# PCB.net
KiCad netlist of a schematic drawn in EAGLE
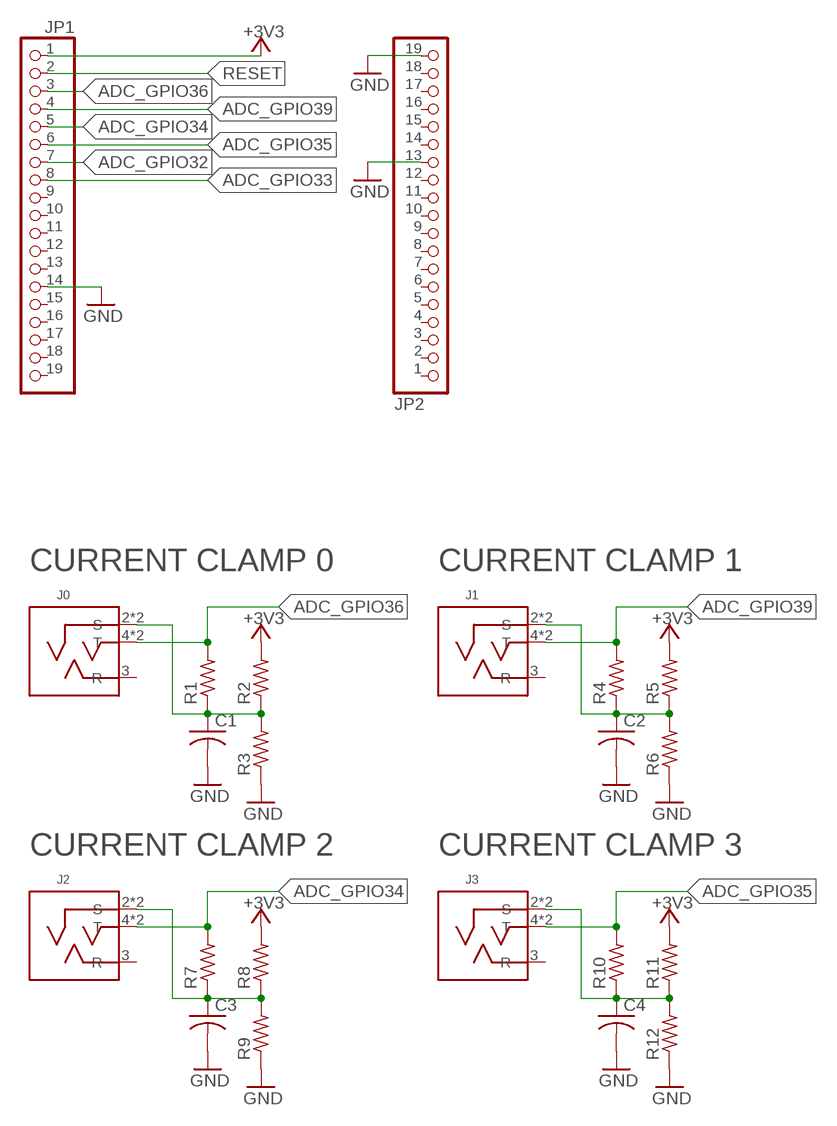
[diagram p0: schematic, sheet 1]

(export (version "E")
  (design (tool "Eeschema 10.0.6"))
  (components
    (comp (ref "C1")
      (value "C-USC1206")
      (footprint "eagle-import:C1206")
      (libsource (lib "eagle-import") (part "C-USC1206"))
    )
    (comp (ref "C2")
      (value "C-USC1206")
      (footprint "eagle-import:C1206")
      (libsource (lib "eagle-import") (part "C-USC1206"))
    )
    (comp (ref "C3")
      (value "C-USC1206")
      (footprint "eagle-import:C1206")
      (libsource (lib "eagle-import") (part "C-USC1206"))
    )
    (comp (ref "C4")
      (value "C-USC1206")
      (footprint "eagle-import:C1206")
      (libsource (lib "eagle-import") (part "C-USC1206"))
    )
    (comp (ref "J0")
      (value "BOOMELE_C18167")
      (footprint "eagle-import:PJ-313")
      (libsource (lib "eagle-import") (part "BOOMELE_C18167"))
    )
    (comp (ref "J1")
      (value "BOOMELE_C18167")
      (footprint "eagle-import:PJ-313")
      (libsource (lib "eagle-import") (part "BOOMELE_C18167"))
    )
    (comp (ref "J2")
      (value "BOOMELE_C18167")
      (footprint "eagle-import:PJ-313")
      (libsource (lib "eagle-import") (part "BOOMELE_C18167"))
    )
    (comp (ref "J3")
      (value "BOOMELE_C18167")
      (footprint "eagle-import:PJ-313")
      (libsource (lib "eagle-import") (part "BOOMELE_C18167"))
    )
    (comp (ref "JP1")
      (value "PINHD-1X19")
      (footprint "eagle-import:1X19")
      (libsource (lib "eagle-import") (part "PINHD-1X19"))
    )
    (comp (ref "JP2")
      (value "PINHD-1X19")
      (footprint "eagle-import:1X19")
      (libsource (lib "eagle-import") (part "PINHD-1X19"))
    )
    (comp (ref "R1")
      (value "R-US_R1206")
      (footprint "eagle-import:R1206")
      (libsource (lib "eagle-import") (part "R-US_R1206"))
    )
    (comp (ref "R2")
      (value "R-US_R1206")
      (footprint "eagle-import:R1206")
      (libsource (lib "eagle-import") (part "R-US_R1206"))
    )
    (comp (ref "R3")
      (value "R-US_R1206")
      (footprint "eagle-import:R1206")
      (libsource (lib "eagle-import") (part "R-US_R1206"))
    )
    (comp (ref "R4")
      (value "R-US_R1206")
      (footprint "eagle-import:R1206")
      (libsource (lib "eagle-import") (part "R-US_R1206"))
    )
    (comp (ref "R5")
      (value "R-US_R1206")
      (footprint "eagle-import:R1206")
      (libsource (lib "eagle-import") (part "R-US_R1206"))
    )
    (comp (ref "R6")
      (value "R-US_R1206")
      (footprint "eagle-import:R1206")
      (libsource (lib "eagle-import") (part "R-US_R1206"))
    )
    (comp (ref "R7")
      (value "R-US_R1206")
      (footprint "eagle-import:R1206")
      (libsource (lib "eagle-import") (part "R-US_R1206"))
    )
    (comp (ref "R8")
      (value "R-US_R1206")
      (footprint "eagle-import:R1206")
      (libsource (lib "eagle-import") (part "R-US_R1206"))
    )
    (comp (ref "R9")
      (value "R-US_R1206")
      (footprint "eagle-import:R1206")
      (libsource (lib "eagle-import") (part "R-US_R1206"))
    )
    (comp (ref "R10")
      (value "R-US_R1206")
      (footprint "eagle-import:R1206")
      (libsource (lib "eagle-import") (part "R-US_R1206"))
    )
    (comp (ref "R11")
      (value "R-US_R1206")
      (footprint "eagle-import:R1206")
      (libsource (lib "eagle-import") (part "R-US_R1206"))
    )
    (comp (ref "R12")
      (value "R-US_R1206")
      (footprint "eagle-import:R1206")
      (libsource (lib "eagle-import") (part "R-US_R1206"))
    )
  )
  (nets
    (net (code "1") (name "+3V3") (class "Default")
      (node (ref "JP1") (pin "1") (pinfunction "1_1") (pintype "passive"))
      (node (ref "R11") (pin "2") (pinfunction "2_2") (pintype "passive"))
      (node (ref "R2") (pin "2") (pinfunction "2_2") (pintype "passive"))
      (node (ref "R5") (pin "2") (pinfunction "2_2") (pintype "passive"))
      (node (ref "R8") (pin "2") (pinfunction "2_2") (pintype "passive"))
    )
    (net (code "2") (name "ADC_GPIO32") (class "Default")
      (node (ref "JP1") (pin "7") (pinfunction "7_7") (pintype "passive"))
    )
    (net (code "3") (name "ADC_GPIO33") (class "Default")
      (node (ref "JP1") (pin "8") (pinfunction "8_8") (pintype "passive"))
    )
    (net (code "4") (name "ADC_GPIO34") (class "Default")
      (node (ref "J2") (pin "4") (pinfunction "T_4") (pintype "bidirectional"))
      (node (ref "J2") (pin "4.") (pinfunction "T_4.") (pintype "bidirectional"))
      (node (ref "JP1") (pin "5") (pinfunction "5_5") (pintype "passive"))
      (node (ref "R7") (pin "2") (pinfunction "2_2") (pintype "passive"))
    )
    (net (code "5") (name "ADC_GPIO35") (class "Default")
      (node (ref "J3") (pin "4") (pinfunction "T_4") (pintype "bidirectional"))
      (node (ref "J3") (pin "4.") (pinfunction "T_4.") (pintype "bidirectional"))
      (node (ref "JP1") (pin "6") (pinfunction "6_6") (pintype "passive"))
      (node (ref "R10") (pin "2") (pinfunction "2_2") (pintype "passive"))
    )
    (net (code "6") (name "ADC_GPIO36") (class "Default")
      (node (ref "J0") (pin "4") (pinfunction "T_4") (pintype "bidirectional"))
      (node (ref "J0") (pin "4.") (pinfunction "T_4.") (pintype "bidirectional"))
      (node (ref "JP1") (pin "3") (pinfunction "3_3") (pintype "passive"))
      (node (ref "R1") (pin "2") (pinfunction "2_2") (pintype "passive"))
    )
    (net (code "7") (name "ADC_GPIO39") (class "Default")
      (node (ref "J1") (pin "4") (pinfunction "T_4") (pintype "bidirectional"))
      (node (ref "J1") (pin "4.") (pinfunction "T_4.") (pintype "bidirectional"))
      (node (ref "JP1") (pin "4") (pinfunction "4_4") (pintype "passive"))
      (node (ref "R4") (pin "2") (pinfunction "2_2") (pintype "passive"))
    )
    (net (code "8") (name "GND") (class "Default")
      (node (ref "C1") (pin "2") (pinfunction "2_2") (pintype "passive"))
      (node (ref "C2") (pin "2") (pinfunction "2_2") (pintype "passive"))
      (node (ref "C3") (pin "2") (pinfunction "2_2") (pintype "passive"))
      (node (ref "C4") (pin "2") (pinfunction "2_2") (pintype "passive"))
      (node (ref "JP1") (pin "14") (pinfunction "14_14") (pintype "passive"))
      (node (ref "JP2") (pin "13") (pinfunction "13_13") (pintype "passive"))
      (node (ref "JP2") (pin "19") (pinfunction "19_19") (pintype "passive"))
      (node (ref "R12") (pin "1") (pinfunction "1_1") (pintype "passive"))
      (node (ref "R3") (pin "1") (pinfunction "1_1") (pintype "passive"))
      (node (ref "R6") (pin "1") (pinfunction "1_1") (pintype "passive"))
      (node (ref "R9") (pin "1") (pinfunction "1_1") (pintype "passive"))
    )
    (net (code "9") (name "Net-(C1-Pad1)") (class "Default")
      (node (ref "C1") (pin "1") (pinfunction "1_1") (pintype "passive"))
      (node (ref "J0") (pin "2") (pinfunction "S_2") (pintype "bidirectional"))
      (node (ref "J0") (pin "2.") (pinfunction "S_2.") (pintype "bidirectional"))
      (node (ref "R1") (pin "1") (pinfunction "1_1") (pintype "passive"))
      (node (ref "R2") (pin "1") (pinfunction "1_1") (pintype "passive"))
      (node (ref "R3") (pin "2") (pinfunction "2_2") (pintype "passive"))
    )
    (net (code "10") (name "Net-(C2-Pad1)") (class "Default")
      (node (ref "C2") (pin "1") (pinfunction "1_1") (pintype "passive"))
      (node (ref "J1") (pin "2") (pinfunction "S_2") (pintype "bidirectional"))
      (node (ref "J1") (pin "2.") (pinfunction "S_2.") (pintype "bidirectional"))
      (node (ref "R4") (pin "1") (pinfunction "1_1") (pintype "passive"))
      (node (ref "R5") (pin "1") (pinfunction "1_1") (pintype "passive"))
      (node (ref "R6") (pin "2") (pinfunction "2_2") (pintype "passive"))
    )
    (net (code "11") (name "Net-(C3-Pad1)") (class "Default")
      (node (ref "C3") (pin "1") (pinfunction "1_1") (pintype "passive"))
      (node (ref "J2") (pin "2") (pinfunction "S_2") (pintype "bidirectional"))
      (node (ref "J2") (pin "2.") (pinfunction "S_2.") (pintype "bidirectional"))
      (node (ref "R7") (pin "1") (pinfunction "1_1") (pintype "passive"))
      (node (ref "R8") (pin "1") (pinfunction "1_1") (pintype "passive"))
      (node (ref "R9") (pin "2") (pinfunction "2_2") (pintype "passive"))
    )
    (net (code "12") (name "Net-(C4-Pad1)") (class "Default")
      (node (ref "C4") (pin "1") (pinfunction "1_1") (pintype "passive"))
      (node (ref "J3") (pin "2") (pinfunction "S_2") (pintype "bidirectional"))
      (node (ref "J3") (pin "2.") (pinfunction "S_2.") (pintype "bidirectional"))
      (node (ref "R10") (pin "1") (pinfunction "1_1") (pintype "passive"))
      (node (ref "R11") (pin "1") (pinfunction "1_1") (pintype "passive"))
      (node (ref "R12") (pin "2") (pinfunction "2_2") (pintype "passive"))
    )
    (net (code "13") (name "RESET") (class "Default")
      (node (ref "JP1") (pin "2") (pinfunction "2_2") (pintype "passive"))
    )
    (net (code "14") (name "unconnected-(J0-R-Pad3)") (class "Default")
      (node (ref "J0") (pin "3") (pinfunction "R_3") (pintype "bidirectional"))
    )
    (net (code "15") (name "unconnected-(J1-R-Pad3)") (class "Default")
      (node (ref "J1") (pin "3") (pinfunction "R_3") (pintype "bidirectional"))
    )
    (net (code "16") (name "unconnected-(J2-R-Pad3)") (class "Default")
      (node (ref "J2") (pin "3") (pinfunction "R_3") (pintype "bidirectional"))
    )
    (net (code "17") (name "unconnected-(J3-R-Pad3)") (class "Default")
      (node (ref "J3") (pin "3") (pinfunction "R_3") (pintype "bidirectional"))
    )
    (net (code "18") (name "unconnected-(JP1-Pad9)") (class "Default")
      (node (ref "JP1") (pin "9") (pinfunction "9_9") (pintype "passive"))
    )
    (net (code "19") (name "unconnected-(JP1-Pad10)") (class "Default")
      (node (ref "JP1") (pin "10") (pinfunction "10_10") (pintype "passive"))
    )
    (net (code "20") (name "unconnected-(JP1-Pad11)") (class "Default")
      (node (ref "JP1") (pin "11") (pinfunction "11_11") (pintype "passive"))
    )
    (net (code "21") (name "unconnected-(JP1-Pad12)") (class "Default")
      (node (ref "JP1") (pin "12") (pinfunction "12_12") (pintype "passive"))
    )
    (net (code "22") (name "unconnected-(JP1-Pad13)") (class "Default")
      (node (ref "JP1") (pin "13") (pinfunction "13_13") (pintype "passive"))
    )
    (net (code "23") (name "unconnected-(JP1-Pad15)") (class "Default")
      (node (ref "JP1") (pin "15") (pinfunction "15_15") (pintype "passive"))
    )
    (net (code "24") (name "unconnected-(JP1-Pad16)") (class "Default")
      (node (ref "JP1") (pin "16") (pinfunction "16_16") (pintype "passive"))
    )
    (net (code "25") (name "unconnected-(JP1-Pad17)") (class "Default")
      (node (ref "JP1") (pin "17") (pinfunction "17_17") (pintype "passive"))
    )
    (net (code "26") (name "unconnected-(JP1-Pad18)") (class "Default")
      (node (ref "JP1") (pin "18") (pinfunction "18_18") (pintype "passive"))
    )
    (net (code "27") (name "unconnected-(JP1-Pad19)") (class "Default")
      (node (ref "JP1") (pin "19") (pinfunction "19_19") (pintype "passive"))
    )
    (net (code "28") (name "unconnected-(JP2-Pad1)") (class "Default")
      (node (ref "JP2") (pin "1") (pinfunction "1_1") (pintype "passive"))
    )
    (net (code "29") (name "unconnected-(JP2-Pad2)") (class "Default")
      (node (ref "JP2") (pin "2") (pinfunction "2_2") (pintype "passive"))
    )
    (net (code "30") (name "unconnected-(JP2-Pad3)") (class "Default")
      (node (ref "JP2") (pin "3") (pinfunction "3_3") (pintype "passive"))
    )
    (net (code "31") (name "unconnected-(JP2-Pad4)") (class "Default")
      (node (ref "JP2") (pin "4") (pinfunction "4_4") (pintype "passive"))
    )
    (net (code "32") (name "unconnected-(JP2-Pad5)") (class "Default")
      (node (ref "JP2") (pin "5") (pinfunction "5_5") (pintype "passive"))
    )
    (net (code "33") (name "unconnected-(JP2-Pad6)") (class "Default")
      (node (ref "JP2") (pin "6") (pinfunction "6_6") (pintype "passive"))
    )
    (net (code "34") (name "unconnected-(JP2-Pad7)") (class "Default")
      (node (ref "JP2") (pin "7") (pinfunction "7_7") (pintype "passive"))
    )
    (net (code "35") (name "unconnected-(JP2-Pad8)") (class "Default")
      (node (ref "JP2") (pin "8") (pinfunction "8_8") (pintype "passive"))
    )
    (net (code "36") (name "unconnected-(JP2-Pad9)") (class "Default")
      (node (ref "JP2") (pin "9") (pinfunction "9_9") (pintype "passive"))
    )
    (net (code "37") (name "unconnected-(JP2-Pad10)") (class "Default")
      (node (ref "JP2") (pin "10") (pinfunction "10_10") (pintype "passive"))
    )
    (net (code "38") (name "unconnected-(JP2-Pad11)") (class "Default")
      (node (ref "JP2") (pin "11") (pinfunction "11_11") (pintype "passive"))
    )
    (net (code "39") (name "unconnected-(JP2-Pad12)") (class "Default")
      (node (ref "JP2") (pin "12") (pinfunction "12_12") (pintype "passive"))
    )
    (net (code "40") (name "unconnected-(JP2-Pad14)") (class "Default")
      (node (ref "JP2") (pin "14") (pinfunction "14_14") (pintype "passive"))
    )
    (net (code "41") (name "unconnected-(JP2-Pad15)") (class "Default")
      (node (ref "JP2") (pin "15") (pinfunction "15_15") (pintype "passive"))
    )
    (net (code "42") (name "unconnected-(JP2-Pad16)") (class "Default")
      (node (ref "JP2") (pin "16") (pinfunction "16_16") (pintype "passive"))
    )
    (net (code "43") (name "unconnected-(JP2-Pad17)") (class "Default")
      (node (ref "JP2") (pin "17") (pinfunction "17_17") (pintype "passive"))
    )
    (net (code "44") (name "unconnected-(JP2-Pad18)") (class "Default")
      (node (ref "JP2") (pin "18") (pinfunction "18_18") (pintype "passive"))
    )
  )
)
